# RHC12.net
KiCad netlist of a schematic drawn in EAGLE
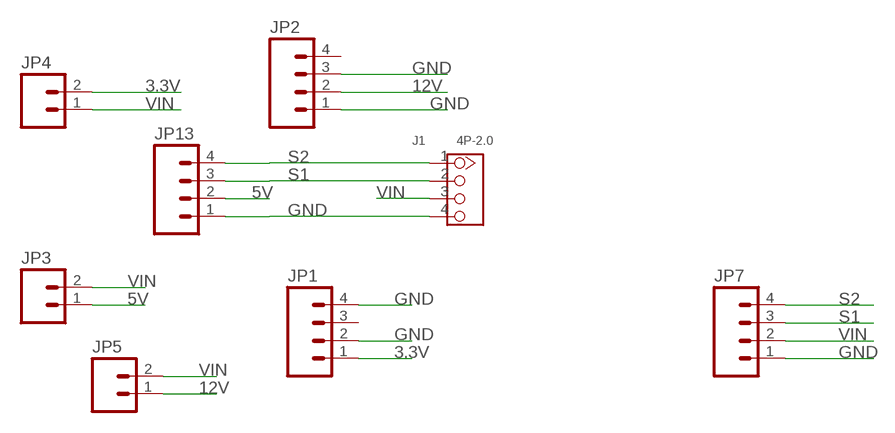
[diagram p0: schematic, sheet 1]

(export (version "E")
  (design (tool "Eeschema 10.0.6"))
  (components
    (comp (ref "J1")
      (value "4P-2.0")
      (footprint "eagle-import:HW4-2.0")
      (libsource (lib "eagle-import") (part "GROVE-CONNECTOR-DIP(4P-2.0)"))
    )
    (comp (ref "JP1")
      (value "M04NO_SILK_ALL_ROUND")
      (footprint "eagle-import:1X04_NO_SILK_ALL_ROUND")
      (libsource (lib "eagle-import") (part "M04NO_SILK_ALL_ROUND"))
    )
    (comp (ref "JP2")
      (value "M04NO_SILK_ALL_ROUND")
      (footprint "eagle-import:1X04_NO_SILK_ALL_ROUND")
      (libsource (lib "eagle-import") (part "M04NO_SILK_ALL_ROUND"))
    )
    (comp (ref "JP3")
      (value "M02PTH")
      (footprint "eagle-import:1X02")
      (libsource (lib "eagle-import") (part "M02PTH"))
    )
    (comp (ref "JP4")
      (value "M02PTH")
      (footprint "eagle-import:1X02")
      (libsource (lib "eagle-import") (part "M02PTH"))
    )
    (comp (ref "JP5")
      (value "M02PTH")
      (footprint "eagle-import:1X02")
      (libsource (lib "eagle-import") (part "M02PTH"))
    )
    (comp (ref "JP7")
      (value "M04PTH")
      (footprint "eagle-import:1X04")
      (libsource (lib "eagle-import") (part "M04PTH"))
    )
    (comp (ref "JP13")
      (value "M04NO_SILK_ALL_ROUND")
      (footprint "eagle-import:1X04_NO_SILK_ALL_ROUND")
      (libsource (lib "eagle-import") (part "M04NO_SILK_ALL_ROUND"))
    )
  )
  (nets
    (net (code "1") (name "/3.3V") (class "Default")
      (node (ref "JP1") (pin "1") (pinfunction "1_1") (pintype "passive"))
      (node (ref "JP4") (pin "2") (pinfunction "2_2") (pintype "passive"))
    )
    (net (code "2") (name "/5V") (class "Default")
      (node (ref "JP13") (pin "2") (pinfunction "2_2") (pintype "passive"))
      (node (ref "JP3") (pin "1") (pinfunction "1_1") (pintype "passive"))
    )
    (net (code "3") (name "/12V") (class "Default")
      (node (ref "JP2") (pin "2") (pinfunction "2_2") (pintype "passive"))
      (node (ref "JP5") (pin "1") (pinfunction "1_1") (pintype "passive"))
    )
    (net (code "4") (name "/GND") (class "Default")
      (node (ref "J1") (pin "4") (pinfunction "4_4") (pintype "bidirectional"))
      (node (ref "JP1") (pin "2") (pinfunction "2_2") (pintype "passive"))
      (node (ref "JP1") (pin "4") (pinfunction "4_4") (pintype "passive"))
      (node (ref "JP13") (pin "1") (pinfunction "1_1") (pintype "passive"))
      (node (ref "JP2") (pin "1") (pinfunction "1_1") (pintype "passive"))
      (node (ref "JP2") (pin "3") (pinfunction "3_3") (pintype "passive"))
      (node (ref "JP7") (pin "1") (pinfunction "1_1") (pintype "passive"))
    )
    (net (code "5") (name "/S1") (class "Default")
      (node (ref "J1") (pin "2") (pinfunction "2_2") (pintype "bidirectional"))
      (node (ref "JP13") (pin "3") (pinfunction "3_3") (pintype "passive"))
      (node (ref "JP7") (pin "3") (pinfunction "3_3") (pintype "passive"))
    )
    (net (code "6") (name "/S2") (class "Default")
      (node (ref "J1") (pin "1") (pinfunction "1_1") (pintype "bidirectional"))
      (node (ref "JP13") (pin "4") (pinfunction "4_4") (pintype "passive"))
      (node (ref "JP7") (pin "4") (pinfunction "4_4") (pintype "passive"))
    )
    (net (code "7") (name "/VIN") (class "Default")
      (node (ref "J1") (pin "3") (pinfunction "3_3") (pintype "bidirectional"))
      (node (ref "JP3") (pin "2") (pinfunction "2_2") (pintype "passive"))
      (node (ref "JP4") (pin "1") (pinfunction "1_1") (pintype "passive"))
      (node (ref "JP5") (pin "2") (pinfunction "2_2") (pintype "passive"))
      (node (ref "JP7") (pin "2") (pinfunction "2_2") (pintype "passive"))
    )
    (net (code "8") (name "unconnected-(JP1-Pad3)") (class "Default")
      (node (ref "JP1") (pin "3") (pinfunction "3_3") (pintype "passive"))
    )
    (net (code "9") (name "unconnected-(JP2-Pad4)") (class "Default")
      (node (ref "JP2") (pin "4") (pinfunction "4_4") (pintype "passive"))
    )
  )
)
